# GPS_IMU.net
KiCad netlist of a schematic drawn in Altium Designer
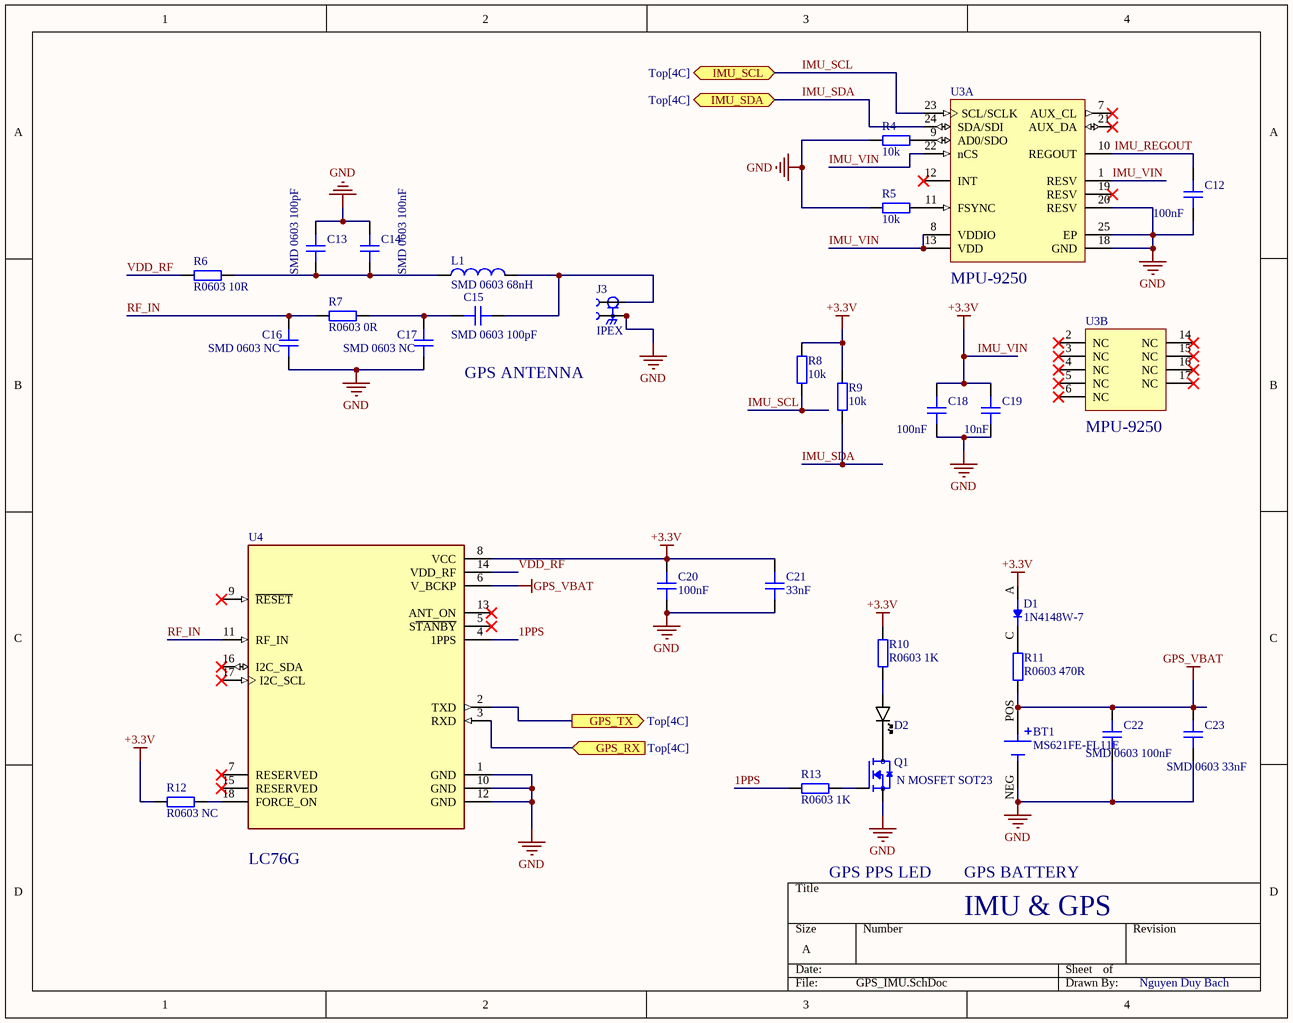
[diagram p0: GPS_IMU.SchDoc]

(export (version "E")
  (design (tool "Eeschema 10.0.6"))
  (components
    (comp (ref "BT1")
      (value "MS621FE-FL11E")
      (footprint "BAT_MS621FE-FL11E")
      (description "Coin, 6.8mm 3 V Lithium Battery Rechargeable (Secondary) 5.5mAh")
      (fields (field (name "MF") "Seiko Instruments"))
      (libsource (lib "Project") (part "MS621FE-FL11E"))
    )
    (comp (ref "C12")
      (value "100nF")
      (footprint "CAP_0603")
      (description "Capacitor SMD 0603")
      (libsource (lib "Project") (part "CAP_0603"))
    )
    (comp (ref "C13")
      (value "SMD 0603 100pF")
      (footprint "CAP_0603")
      (description "Capacitor SMD 0603")
      (libsource (lib "Project") (part "CAP_0603"))
    )
    (comp (ref "C14")
      (value "SMD 0603 100nF")
      (footprint "CAP_0603")
      (description "Capacitor SMD 0603")
      (libsource (lib "Project") (part "CAP_0603"))
    )
    (comp (ref "C15")
      (value "SMD 0603 100pF")
      (footprint "CAP_0603")
      (description "Capacitor SMD 0603")
      (libsource (lib "Project") (part "CAP_0603"))
    )
    (comp (ref "C16")
      (value "SMD 0603 NC")
      (footprint "NC_0603")
      (description "Capacitor SMD 0603")
      (libsource (lib "Project") (part "CAP_0603"))
    )
    (comp (ref "C17")
      (value "SMD 0603 NC")
      (footprint "NC_0603")
      (description "Capacitor SMD 0603")
      (libsource (lib "Project") (part "CAP_0603"))
    )
    (comp (ref "C18")
      (value "100nF")
      (footprint "CAP_0603")
      (description "Capacitor SMD 0603")
      (libsource (lib "Project") (part "CAP_0603"))
    )
    (comp (ref "C19")
      (value "10nF")
      (footprint "CAP_0603")
      (description "Capacitor SMD 0603")
      (libsource (lib "Project") (part "CAP_0603"))
    )
    (comp (ref "C20")
      (value "100nF")
      (footprint "CAP_0603")
      (description "Capacitor SMD 0603")
      (libsource (lib "Project") (part "CAP_0603"))
    )
    (comp (ref "C21")
      (value "33nF")
      (footprint "CAP_0603")
      (description "Capacitor SMD 0603")
      (libsource (lib "Project") (part "CAP_0603"))
    )
    (comp (ref "C22")
      (value "SMD 0603 100nF")
      (footprint "CAP_0603")
      (description "Capacitor SMD 0603")
      (libsource (lib "Project") (part "CAP_0603"))
    )
    (comp (ref "C23")
      (value "SMD 0603 33nF")
      (footprint "CAP_0603")
      (description "Capacitor SMD 0603")
      (libsource (lib "Project") (part "CAP_0603"))
    )
    (comp (ref "D1")
      (value "1N4148W-7")
      (footprint "SOD3715X135N")
      (description "Diode Standard 100 V 300mA (DC) Surface Mount SOD-123")
      (fields (field (name "MF") "Diodes Inc."))
      (libsource (lib "Project") (part "1N4148W-7"))
    )
    (comp (ref "D2")
      (value "BLUE")
      (footprint "LED_0805")
      (description "LED 0805 BLUE SMD")
      (libsource (lib "Project") (part "LED_0805"))
    )
    (comp (ref "J3")
      (value "IPEX")
      (footprint "IPEX_20279-001E-03")
      (fields (field (name "MF") "I-PEX") (field (name "MP") "20279-001E-03"))
      (libsource (lib "Project") (part "IPEX"))
    )
    (comp (ref "L1")
      (value "SMD 0603 68nH")
      (footprint "0603 INDUCTOR")
      (description "Inductor with 0603 (1608)")
      (fields (field (name "MP") "LQW18AS22NG0CD") (field (name "MF") "Murata"))
      (libsource (lib "Project") (part "INDUCTOR_0603"))
    )
    (comp (ref "Q1")
      (value "N MOSFET SOT23")
      (footprint "SOT95P237X112-3N")
      (description "N-Channel 30 V 3.16A (Ta) 750mW (Ta) Surface Mount SOT-23-3 (TO-236)")
      (fields (field (name "MF") "Vishay Siliconix") (field (name "MP") "SI2306BDS-T1-GE3"))
      (libsource (lib "Project") (part "SI2306BDS-T1-GE3"))
    )
    (comp (ref "R4")
      (value "10k")
      (footprint "RES_0603")
      (description "Resistor SMD 0603")
      (libsource (lib "Project") (part "RES_0603"))
    )
    (comp (ref "R5")
      (value "10k")
      (footprint "RES_0603")
      (description "Resistor SMD 0603")
      (libsource (lib "Project") (part "RES_0603"))
    )
    (comp (ref "R6")
      (value "R0603 10R")
      (footprint "RES_0603")
      (description "Resistor SMD 0603")
      (libsource (lib "Project") (part "RES_0603"))
    )
    (comp (ref "R7")
      (value "R0603 0R")
      (footprint "RES_0603")
      (description "Resistor SMD 0603")
      (libsource (lib "Project") (part "RES_0603"))
    )
    (comp (ref "R8")
      (value "10k")
      (footprint "RES_0603")
      (description "Resistor SMD 0603")
      (libsource (lib "Project") (part "RES_0603"))
    )
    (comp (ref "R9")
      (value "10k")
      (footprint "RES_0603")
      (description "Resistor SMD 0603")
      (libsource (lib "Project") (part "RES_0603"))
    )
    (comp (ref "R10")
      (value "R0603 1K")
      (footprint "RES_0603")
      (description "Resistor SMD 0603")
      (libsource (lib "Project") (part "RES_0603"))
    )
    (comp (ref "R11")
      (value "R0603 470R")
      (footprint "RES_0603")
      (description "Resistor SMD 0603")
      (libsource (lib "Project") (part "RES_0603"))
    )
    (comp (ref "R12")
      (value "R0603 NC")
      (footprint "NC_0603")
      (description "Resistor SMD 0603")
      (libsource (lib "Project") (part "RES_0603"))
    )
    (comp (ref "R13")
      (value "R0603 1K")
      (footprint "RES_0603")
      (description "Resistor SMD 0603")
      (libsource (lib "Project") (part "RES_0603"))
    )
    (comp (ref "U3")
      (value "MPU-9250")
      (footprint "INSE-QFN-24-1700X1540TP_M")
      (description "9-axis MotionTracking device, 2.4 to 3,6 V, -40 to 85 degC, 24-Pin QFN, RoHS, Tape and Reel")
      (fields (field (name "MANUFACTURER") "InvenSense"))
      (libsource (lib "Altium Content Vault") (part "INSE-MPU-9250-QFN-24"))
    )
    (comp (ref "U4")
      (value "LC76G")
      (footprint "XCVR_LC76G")
      (fields (field (name "MF") "Quectel"))
      (libsource (lib "Project") (part "LC76G"))
    )
  )
  (nets
    (net (code "1") (name "+3.3V") (class "Default")
      (node (ref "C18") (pin "2") (pinfunction "2_2") (pintype "passive"))
      (node (ref "C19") (pin "2") (pinfunction "2_2") (pintype "passive"))
      (node (ref "C20") (pin "2") (pinfunction "2_2") (pintype "passive"))
      (node (ref "C21") (pin "2") (pinfunction "2_2") (pintype "passive"))
      (node (ref "D1") (pin "A") (pinfunction "A_A") (pintype "passive"))
      (node (ref "R10") (pin "2") (pinfunction "2_2") (pintype "passive"))
      (node (ref "R12") (pin "1") (pinfunction "1_1") (pintype "passive"))
      (node (ref "R8") (pin "2") (pinfunction "2_2") (pintype "passive"))
      (node (ref "R9") (pin "2") (pinfunction "2_2") (pintype "passive"))
      (node (ref "U3") (pin "1") (pinfunction "RESV_1") (pintype "power_in"))
      (node (ref "U3") (pin "13") (pinfunction "VDD_13") (pintype "power_in"))
      (node (ref "U3") (pin "22") (pinfunction "nCS_22") (pintype "input"))
      (node (ref "U3") (pin "8") (pinfunction "VDDIO_8") (pintype "power_in"))
      (node (ref "U4") (pin "8") (pinfunction "VCC_8") (pintype "power_in"))
    )
    (net (code "2") (name "/1PPS") (class "Default")
      (node (ref "R13") (pin "2") (pinfunction "2_2") (pintype "passive"))
      (node (ref "U4") (pin "4") (pinfunction "1PPS_4") (pintype "passive"))
    )
    (net (code "3") (name "/GPS_RX") (class "Default")
      (node (ref "U4") (pin "3") (pinfunction "RXD_3") (pintype "input"))
    )
    (net (code "4") (name "/GPS_TX") (class "Default")
      (node (ref "U4") (pin "2") (pinfunction "TXD_2") (pintype "output"))
    )
    (net (code "5") (name "/IMU_REGOUT") (class "Default")
      (node (ref "C12") (pin "2") (pinfunction "2_2") (pintype "passive"))
      (node (ref "U3") (pin "10") (pinfunction "REGOUT_10") (pintype "passive"))
    )
    (net (code "6") (name "/IMU_SCL") (class "Default")
      (node (ref "R8") (pin "1") (pinfunction "1_1") (pintype "passive"))
      (node (ref "U3") (pin "23") (pinfunction "SCL/SCLK_23") (pintype "input"))
    )
    (net (code "7") (name "/IMU_SDA") (class "Default")
      (node (ref "R9") (pin "1") (pinfunction "1_1") (pintype "passive"))
      (node (ref "U3") (pin "24") (pinfunction "SDA/SDI_24") (pintype "bidirectional"))
    )
    (net (code "8") (name "/RF_IN") (class "Default")
      (node (ref "C16") (pin "1") (pinfunction "1_1") (pintype "passive"))
      (node (ref "R7") (pin "1") (pinfunction "1_1") (pintype "passive"))
      (node (ref "U4") (pin "11") (pinfunction "RF_IN_11") (pintype "input"))
    )
    (net (code "9") (name "/VDD_RF") (class "Default")
      (node (ref "R6") (pin "1") (pinfunction "1_1") (pintype "passive"))
      (node (ref "U4") (pin "14") (pinfunction "VDD_RF_14") (pintype "power_in"))
    )
    (net (code "10") (name "GND") (class "Default")
      (node (ref "BT1") (pin "NEG") (pinfunction "NEG_NEG") (pintype "passive"))
      (node (ref "C12") (pin "1") (pinfunction "1_1") (pintype "passive"))
      (node (ref "C13") (pin "2") (pinfunction "2_2") (pintype "passive"))
      (node (ref "C14") (pin "2") (pinfunction "2_2") (pintype "passive"))
      (node (ref "C16") (pin "2") (pinfunction "2_2") (pintype "passive"))
      (node (ref "C17") (pin "2") (pinfunction "2_2") (pintype "passive"))
      (node (ref "C18") (pin "1") (pinfunction "1_1") (pintype "passive"))
      (node (ref "C19") (pin "1") (pinfunction "1_1") (pintype "passive"))
      (node (ref "C20") (pin "1") (pinfunction "1_1") (pintype "passive"))
      (node (ref "C21") (pin "1") (pinfunction "1_1") (pintype "passive"))
      (node (ref "C22") (pin "1") (pinfunction "1_1") (pintype "passive"))
      (node (ref "C23") (pin "1") (pinfunction "1_1") (pintype "passive"))
      (node (ref "J3") (pin "2") (pinfunction "GROUND_2") (pintype "passive"))
      (node (ref "J3") (pin "3") (pinfunction "GROUND_3") (pintype "passive"))
      (node (ref "Q1") (pin "2") (pinfunction "S_2") (pintype "passive"))
      (node (ref "R4") (pin "2") (pinfunction "2_2") (pintype "passive"))
      (node (ref "R5") (pin "2") (pinfunction "2_2") (pintype "passive"))
      (node (ref "U3") (pin "18") (pinfunction "GND_18") (pintype "power_in"))
      (node (ref "U3") (pin "20") (pinfunction "RESV_20") (pintype "power_in"))
      (node (ref "U3") (pin "25") (pinfunction "EP_25") (pintype "passive"))
      (node (ref "U4") (pin "1") (pinfunction "GND_1") (pintype "power_in"))
      (node (ref "U4") (pin "10") (pinfunction "GND_10") (pintype "power_in"))
      (node (ref "U4") (pin "12") (pinfunction "GND_12") (pintype "power_in"))
    )
    (net (code "11") (name "GPS_VBAT") (class "Default")
      (node (ref "BT1") (pin "POS") (pinfunction "POS_POS") (pintype "passive"))
      (node (ref "C22") (pin "2") (pinfunction "2_2") (pintype "passive"))
      (node (ref "C23") (pin "2") (pinfunction "2_2") (pintype "passive"))
      (node (ref "R11") (pin "1") (pinfunction "1_1") (pintype "passive"))
      (node (ref "U4") (pin "6") (pinfunction "V_BCKP_6") (pintype "power_in"))
    )
    (net (code "12") (name "Net-(C13-Pad1)") (class "Default")
      (node (ref "C13") (pin "1") (pinfunction "1_1") (pintype "passive"))
      (node (ref "C14") (pin "1") (pinfunction "1_1") (pintype "passive"))
      (node (ref "L1") (pin "1") (pinfunction "1_1") (pintype "passive"))
      (node (ref "R6") (pin "2") (pinfunction "2_2") (pintype "passive"))
    )
    (net (code "13") (name "Net-(C15-Pad1)") (class "Default")
      (node (ref "C15") (pin "1") (pinfunction "1_1") (pintype "passive"))
      (node (ref "C17") (pin "1") (pinfunction "1_1") (pintype "passive"))
      (node (ref "R7") (pin "2") (pinfunction "2_2") (pintype "passive"))
    )
    (net (code "14") (name "Net-(D1-K)") (class "Default")
      (node (ref "D1") (pin "C") (pinfunction "K_C") (pintype "passive"))
      (node (ref "R11") (pin "2") (pinfunction "2_2") (pintype "passive"))
    )
    (net (code "15") (name "Net-(D2-PadA)") (class "Default")
      (node (ref "D2") (pin "A") (pinfunction "A_A") (pintype "passive"))
      (node (ref "R10") (pin "1") (pinfunction "1_1") (pintype "passive"))
    )
    (net (code "16") (name "Net-(J3-SIGNAL)") (class "Default")
      (node (ref "C15") (pin "2") (pinfunction "2_2") (pintype "passive"))
      (node (ref "J3") (pin "1") (pinfunction "SIGNAL_1") (pintype "passive"))
      (node (ref "L1") (pin "2") (pinfunction "2_2") (pintype "passive"))
    )
    (net (code "17") (name "Net-(Q1-D)") (class "Default")
      (node (ref "D2") (pin "K") (pinfunction "K_K") (pintype "passive"))
      (node (ref "Q1") (pin "3") (pinfunction "D_3") (pintype "passive"))
    )
    (net (code "18") (name "Net-(Q1-G)") (class "Default")
      (node (ref "Q1") (pin "1") (pinfunction "G_1") (pintype "passive"))
      (node (ref "R13") (pin "1") (pinfunction "1_1") (pintype "passive"))
    )
    (net (code "19") (name "Net-(U3A-AD0{slash}SDO)") (class "Default")
      (node (ref "R4") (pin "1") (pinfunction "1_1") (pintype "passive"))
      (node (ref "U3") (pin "9") (pinfunction "AD0/SDO_9") (pintype "bidirectional"))
    )
    (net (code "20") (name "Net-(U3A-FSYNC)") (class "Default")
      (node (ref "R5") (pin "1") (pinfunction "1_1") (pintype "passive"))
      (node (ref "U3") (pin "11") (pinfunction "FSYNC_11") (pintype "input"))
    )
    (net (code "21") (name "Net-(U4-FORCE_ON)") (class "Default")
      (node (ref "R12") (pin "2") (pinfunction "2_2") (pintype "passive"))
      (node (ref "U4") (pin "18") (pinfunction "FORCE_ON_18") (pintype "passive"))
    )
    (net (code "22") (name "unconnected-(U3A-AUX_CL-Pad7)") (class "Default")
      (node (ref "U3") (pin "7") (pinfunction "AUX_CL_7") (pintype "output+no_connect"))
    )
    (net (code "23") (name "unconnected-(U3A-AUX_DA-Pad21)") (class "Default")
      (node (ref "U3") (pin "21") (pinfunction "AUX_DA_21") (pintype "bidirectional+no_connect"))
    )
    (net (code "24") (name "unconnected-(U3A-INT-Pad12)") (class "Default")
      (node (ref "U3") (pin "12") (pinfunction "INT_12") (pintype "tri_state+no_connect"))
    )
    (net (code "25") (name "unconnected-(U3A-RESV-Pad19)") (class "Default")
      (node (ref "U3") (pin "19") (pinfunction "RESV_19") (pintype "passive+no_connect"))
    )
    (net (code "26") (name "unconnected-(U3B-NC-Pad2)") (class "Default")
      (node (ref "U3") (pin "2") (pinfunction "NC_2") (pintype "passive+no_connect"))
    )
    (net (code "27") (name "unconnected-(U3B-NC-Pad3)") (class "Default")
      (node (ref "U3") (pin "3") (pinfunction "NC_3") (pintype "passive+no_connect"))
    )
    (net (code "28") (name "unconnected-(U3B-NC-Pad4)") (class "Default")
      (node (ref "U3") (pin "4") (pinfunction "NC_4") (pintype "passive+no_connect"))
    )
    (net (code "29") (name "unconnected-(U3B-NC-Pad5)") (class "Default")
      (node (ref "U3") (pin "5") (pinfunction "NC_5") (pintype "passive+no_connect"))
    )
    (net (code "30") (name "unconnected-(U3B-NC-Pad6)") (class "Default")
      (node (ref "U3") (pin "6") (pinfunction "NC_6") (pintype "passive+no_connect"))
    )
    (net (code "31") (name "unconnected-(U3B-NC-Pad14)") (class "Default")
      (node (ref "U3") (pin "14") (pinfunction "NC_14") (pintype "passive+no_connect"))
    )
    (net (code "32") (name "unconnected-(U3B-NC-Pad15)") (class "Default")
      (node (ref "U3") (pin "15") (pinfunction "NC_15") (pintype "passive+no_connect"))
    )
    (net (code "33") (name "unconnected-(U3B-NC-Pad16)") (class "Default")
      (node (ref "U3") (pin "16") (pinfunction "NC_16") (pintype "passive+no_connect"))
    )
    (net (code "34") (name "unconnected-(U3B-NC-Pad17)") (class "Default")
      (node (ref "U3") (pin "17") (pinfunction "NC_17") (pintype "passive+no_connect"))
    )
    (net (code "35") (name "unconnected-(U4-ANT_ON-Pad13)") (class "Default")
      (node (ref "U4") (pin "13") (pinfunction "ANT_ON_13") (pintype "passive+no_connect"))
    )
    (net (code "36") (name "unconnected-(U4-I2C_SCL-Pad17)") (class "Default")
      (node (ref "U4") (pin "17") (pinfunction "I2C_SCL_17") (pintype "input+no_connect"))
    )
    (net (code "37") (name "unconnected-(U4-I2C_SDA-Pad16)") (class "Default")
      (node (ref "U4") (pin "16") (pinfunction "I2C_SDA_16") (pintype "bidirectional+no_connect"))
    )
    (net (code "38") (name "unconnected-(U4-RESERVED-Pad7)") (class "Default")
      (node (ref "U4") (pin "7") (pinfunction "RESERVED_7") (pintype "passive+no_connect"))
    )
    (net (code "39") (name "unconnected-(U4-RESERVED-Pad15)") (class "Default")
      (node (ref "U4") (pin "15") (pinfunction "RESERVED_15") (pintype "passive+no_connect"))
    )
    (net (code "40") (name "unconnected-(U4-S~{TANBY}-Pad5)") (class "Default")
      (node (ref "U4") (pin "5") (pinfunction "S~{TANBY}_5") (pintype "passive+no_connect"))
    )
    (net (code "41") (name "unconnected-(U4-~{RESET}-Pad9)") (class "Default")
      (node (ref "U4") (pin "9") (pinfunction "~{RESET}_9") (pintype "input+no_connect"))
    )
  )
)
